# Fused_485.net
KiCad netlist of a schematic drawn in Altium Designer
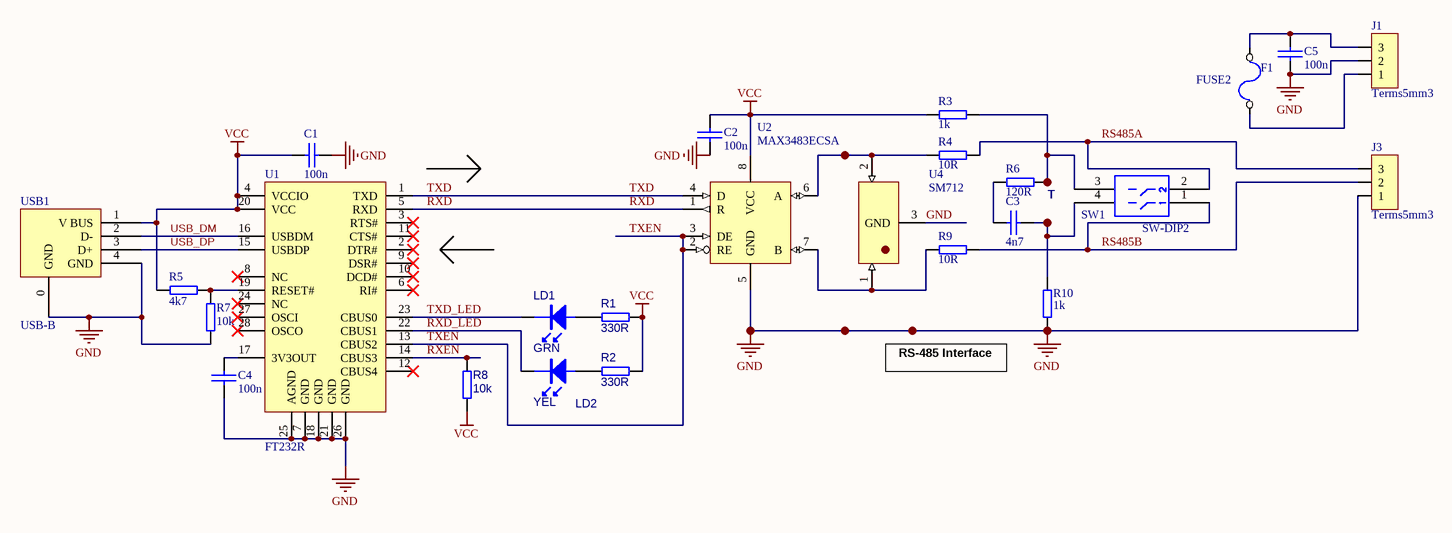
[diagram p0: Fused_485.SchDoc]

(export (version "E")
  (design (tool "Eeschema 10.0.6"))
  (components
    (comp (ref "C1") (value "100n") (footprint "0603") (libsource (lib "*") (part "CAP")))
    (comp (ref "C2") (value "100n") (footprint "0603") (libsource (lib "*") (part "CAP")))
    (comp (ref "C3") (value "4n7") (footprint "0603") (libsource (lib "*") (part "CAP")))
    (comp (ref "C4") (value "100n") (footprint "0603") (libsource (lib "*") (part "CAP")))
    (comp (ref "C5") (value "100n") (footprint "0603") (libsource (lib "*") (part "CAP")))
    (comp (ref "F1") (value "FUSE2") (footprint "Fuse_auto") (libsource (lib "DEVICE") (part "FUSE2")))
    (comp (ref "J1") (value "Terms5mm3") (footprint "TERMS5mm3") (libsource (lib "DEVICE") (part "CON3")))
    (comp (ref "J3") (value "Terms5mm3") (footprint "TERMS5mm3") (libsource (lib "DEVICE") (part "CON3")))
    (comp (ref "LD1") (value "GRN") (footprint "0805DIODE") (libsource (lib "*") (part "LED")))
    (comp (ref "LD2") (value "YEL") (footprint "0805DIODE") (libsource (lib "*") (part "LED")))
    (comp (ref "R1") (value "330R") (footprint "0603") (libsource (lib "DEVICE") (part "RES8")))
    (comp (ref "R2") (value "330R") (footprint "0603") (libsource (lib "DEVICE") (part "RES8")))
    (comp (ref "R3") (value "1k") (footprint "0603") (libsource (lib "*") (part "RES8")))
    (comp (ref "R4") (value "10R") (footprint "0603") (libsource (lib "*") (part "RES8")))
    (comp (ref "R5") (value "4k7") (footprint "0603") (libsource (lib "DEVICE") (part "RES8")))
    (comp (ref "R6") (value "120R") (footprint "0603") (libsource (lib "*") (part "RES8")))
    (comp (ref "R7") (value "10k") (footprint "0603") (libsource (lib "DEVICE") (part "RES8")))
    (comp (ref "R8") (value "10k") (footprint "0603") (libsource (lib "DEVICE") (part "RES8")))
    (comp (ref "R9") (value "10R") (footprint "0603") (libsource (lib "*") (part "RES8")))
    (comp (ref "R10") (value "1k") (footprint "0603") (libsource (lib "*") (part "RES8")))
    (comp (ref "SW1") (value "SW-DIP2") (footprint "DIP4") (libsource (lib "*") (part "SW-DIP2")))
    (comp (ref "U1")
      (value "FT232R")
      (footprint "SSOP28W-handsolder")
      (libsource (lib "FTDI") (part "FT232R"))
    )
    (comp (ref "U2")
      (value "MAX3483ECSA")
      (footprint "so-8")
      (description "RS485 Transceiver")
      (libsource (lib "*") (part "MAX487"))
    )
    (comp (ref "U4")
      (value "SM712")
      (footprint "sot-23")
      (description "RS485 Transorb")
      (fields (field (name "PARTNO.") "2059024"))
      (libsource (lib "TomsSchLib") (part "SM712"))
    )
    (comp (ref "USB1") (value "USB-B") (footprint "USB_B") (libsource (lib "DEVICE") (part "USB-B")))
  )
  (nets
    (net (code "1") (name "/RS485A") (class "Default")
      (node (ref "J3") (pin "3") (pinfunction "3_3") (pintype "passive"))
      (node (ref "R4") (pin "2") (pintype "passive"))
      (node (ref "SW1") (pin "2") (pintype "passive"))
    )
    (net (code "2") (name "/RS485B") (class "Default")
      (node (ref "J3") (pin "2") (pinfunction "2_2") (pintype "passive"))
      (node (ref "R9") (pin "2") (pintype "passive"))
      (node (ref "SW1") (pin "1") (pintype "passive"))
    )
    (net (code "3") (name "/RXD") (class "Default")
      (node (ref "U1") (pin "5") (pinfunction "RXD_5") (pintype "passive"))
      (node (ref "U2") (pin "1") (pinfunction "R_1") (pintype "output"))
    )
    (net (code "4") (name "/RXD_LED") (class "Default")
      (node (ref "LD2") (pin "K") (pintype "passive"))
      (node (ref "U1") (pin "22") (pinfunction "CBUS1_22") (pintype "passive"))
    )
    (net (code "5") (name "/RXEN") (class "Default")
      (node (ref "R8") (pin "2") (pintype "passive"))
      (node (ref "U1") (pin "14") (pinfunction "CBUS3_14") (pintype "passive"))
    )
    (net (code "6") (name "/TXD") (class "Default")
      (node (ref "U1") (pin "1") (pinfunction "TXD_1") (pintype "passive"))
      (node (ref "U2") (pin "4") (pinfunction "D_4") (pintype "input"))
    )
    (net (code "7") (name "/TXD_LED") (class "Default")
      (node (ref "LD1") (pin "K") (pintype "passive"))
      (node (ref "U1") (pin "23") (pinfunction "CBUS0_23") (pintype "passive"))
    )
    (net (code "8") (name "/TXEN") (class "Default")
      (node (ref "U1") (pin "13") (pinfunction "CBUS2_13") (pintype "passive"))
      (node (ref "U2") (pin "2") (pinfunction "RE_2") (pintype "input"))
      (node (ref "U2") (pin "3") (pinfunction "DE_3") (pintype "input"))
    )
    (net (code "9") (name "/USB_DM") (class "Default")
      (node (ref "U1") (pin "16") (pinfunction "USBDM_16") (pintype "passive"))
      (node (ref "USB1") (pin "2") (pinfunction "D-_2") (pintype "passive"))
    )
    (net (code "10") (name "/USB_DP") (class "Default")
      (node (ref "U1") (pin "15") (pinfunction "USBDP_15") (pintype "passive"))
      (node (ref "USB1") (pin "3") (pinfunction "D+_3") (pintype "passive"))
    )
    (net (code "11") (name "GND") (class "Default")
      (node (ref "C1") (pin "1") (pintype "passive"))
      (node (ref "C2") (pin "2") (pintype "passive"))
      (node (ref "C4") (pin "1") (pintype "passive"))
      (node (ref "C5") (pin "2") (pintype "passive"))
      (node (ref "J1") (pin "2") (pinfunction "2_2") (pintype "passive"))
      (node (ref "J3") (pin "1") (pinfunction "1_1") (pintype "passive"))
      (node (ref "R10") (pin "2") (pintype "passive"))
      (node (ref "R7") (pin "1") (pintype "passive"))
      (node (ref "U1") (pin "18") (pinfunction "GND_18") (pintype "passive"))
      (node (ref "U1") (pin "21") (pinfunction "GND_21") (pintype "passive"))
      (node (ref "U1") (pin "25") (pinfunction "AGND_25") (pintype "passive"))
      (node (ref "U1") (pin "26") (pinfunction "GND_26") (pintype "passive"))
      (node (ref "U1") (pin "7") (pinfunction "GND_7") (pintype "passive"))
      (node (ref "U2") (pin "5") (pinfunction "GND_5") (pintype "power_in"))
      (node (ref "U4") (pin "3") (pinfunction "GND_3") (pintype "power_in"))
      (node (ref "USB1") (pin "0") (pinfunction "GND_0") (pintype "power_in"))
      (node (ref "USB1") (pin "4") (pinfunction "GND_4") (pintype "passive"))
    )
    (net (code "12") (name "Net-(C3-Pad1)") (class "Default")
      (node (ref "C3") (pin "1") (pintype "passive"))
      (node (ref "R6") (pin "1") (pintype "passive"))
    )
    (net (code "13") (name "Net-(C3-Pad2)") (class "Default")
      (node (ref "C3") (pin "2") (pintype "passive"))
      (node (ref "R10") (pin "1") (pintype "passive"))
      (node (ref "SW1") (pin "4") (pintype "passive"))
    )
    (net (code "14") (name "Net-(C5-Pad1)") (class "Default")
      (node (ref "C5") (pin "1") (pintype "passive"))
      (node (ref "F1") (pin "2") (pintype "passive"))
      (node (ref "J1") (pin "3") (pinfunction "3_3") (pintype "passive"))
    )
    (net (code "15") (name "Net-(F1-Pad1)") (class "Default")
      (node (ref "F1") (pin "1") (pintype "passive"))
      (node (ref "J1") (pin "1") (pinfunction "1_1") (pintype "passive"))
    )
    (net (code "16") (name "Net-(LD1-PadA)") (class "Default")
      (node (ref "LD1") (pin "A") (pintype "passive"))
      (node (ref "R1") (pin "2") (pintype "passive"))
    )
    (net (code "17") (name "Net-(LD2-PadA)") (class "Default")
      (node (ref "LD2") (pin "A") (pintype "passive"))
      (node (ref "R2") (pin "2") (pintype "passive"))
    )
    (net (code "18") (name "Net-(R3-Pad2)") (class "Default")
      (node (ref "R3") (pin "2") (pintype "passive"))
      (node (ref "R6") (pin "2") (pintype "passive"))
      (node (ref "SW1") (pin "3") (pintype "passive"))
    )
    (net (code "19") (name "Net-(U1-3V3OUT)") (class "Default")
      (node (ref "C4") (pin "2") (pintype "passive"))
      (node (ref "U1") (pin "17") (pinfunction "3V3OUT_17") (pintype "passive"))
    )
    (net (code "20") (name "Net-(U1-RESET#)") (class "Default")
      (node (ref "R5") (pin "2") (pintype "passive"))
      (node (ref "R7") (pin "2") (pintype "passive"))
      (node (ref "U1") (pin "19") (pinfunction "RESET#_19") (pintype "passive"))
    )
    (net (code "21") (name "Net-(U2-A)") (class "Default")
      (node (ref "R4") (pin "1") (pintype "passive"))
      (node (ref "U2") (pin "6") (pinfunction "A_6") (pintype "bidirectional"))
      (node (ref "U4") (pin "2") (pintype "input"))
    )
    (net (code "22") (name "Net-(U2-B)") (class "Default")
      (node (ref "R9") (pin "1") (pintype "passive"))
      (node (ref "U2") (pin "7") (pinfunction "B_7") (pintype "bidirectional"))
      (node (ref "U4") (pin "1") (pintype "input"))
    )
    (net (code "23") (name "VCC") (class "Default")
      (node (ref "C1") (pin "2") (pintype "passive"))
      (node (ref "C2") (pin "1") (pintype "passive"))
      (node (ref "R1") (pin "1") (pintype "passive"))
      (node (ref "R2") (pin "1") (pintype "passive"))
      (node (ref "R3") (pin "1") (pintype "passive"))
      (node (ref "R5") (pin "1") (pintype "passive"))
      (node (ref "R8") (pin "1") (pintype "passive"))
      (node (ref "U1") (pin "20") (pinfunction "VCC_20") (pintype "passive"))
      (node (ref "U1") (pin "4") (pinfunction "VCCIO_4") (pintype "passive"))
      (node (ref "U2") (pin "8") (pinfunction "VCC_8") (pintype "power_in"))
      (node (ref "USB1") (pin "1") (pinfunction "V_BUS_1") (pintype "passive"))
    )
    (net (code "24") (name "unconnected-(U1-CBUS4-Pad12)") (class "Default")
      (node (ref "U1") (pin "12") (pinfunction "CBUS4_12") (pintype "passive+no_connect"))
    )
    (net (code "25") (name "unconnected-(U1-CTS#-Pad11)") (class "Default")
      (node (ref "U1") (pin "11") (pinfunction "CTS#_11") (pintype "passive+no_connect"))
    )
    (net (code "26") (name "unconnected-(U1-DCD#-Pad10)") (class "Default")
      (node (ref "U1") (pin "10") (pinfunction "DCD#_10") (pintype "passive+no_connect"))
    )
    (net (code "27") (name "unconnected-(U1-DSR#-Pad9)") (class "Default")
      (node (ref "U1") (pin "9") (pinfunction "DSR#_9") (pintype "passive+no_connect"))
    )
    (net (code "28") (name "unconnected-(U1-DTR#-Pad2)") (class "Default")
      (node (ref "U1") (pin "2") (pinfunction "DTR#_2") (pintype "passive+no_connect"))
    )
    (net (code "29") (name "unconnected-(U1-NC-Pad8)") (class "Default")
      (node (ref "U1") (pin "8") (pinfunction "NC_8") (pintype "passive+no_connect"))
    )
    (net (code "30") (name "unconnected-(U1-NC-Pad24)") (class "Default")
      (node (ref "U1") (pin "24") (pinfunction "NC_24") (pintype "passive+no_connect"))
    )
    (net (code "31") (name "unconnected-(U1-OSCI-Pad27)") (class "Default")
      (node (ref "U1") (pin "27") (pinfunction "OSCI_27") (pintype "passive+no_connect"))
    )
    (net (code "32") (name "unconnected-(U1-OSCO-Pad28)") (class "Default")
      (node (ref "U1") (pin "28") (pinfunction "OSCO_28") (pintype "passive+no_connect"))
    )
    (net (code "33") (name "unconnected-(U1-RI#-Pad6)") (class "Default")
      (node (ref "U1") (pin "6") (pinfunction "RI#_6") (pintype "passive+no_connect"))
    )
    (net (code "34") (name "unconnected-(U1-RTS#-Pad3)") (class "Default")
      (node (ref "U1") (pin "3") (pinfunction "RTS#_3") (pintype "passive+no_connect"))
    )
  )
)
